# U_WE_BOX.net
KiCad netlist of a schematic drawn in EAGLE
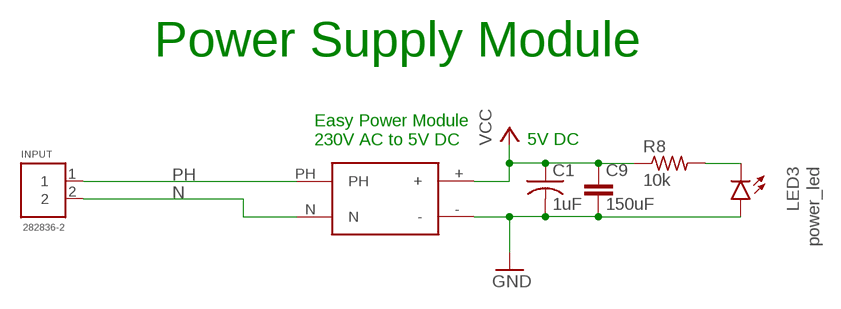
[diagram p0: schematic, sheet 1]
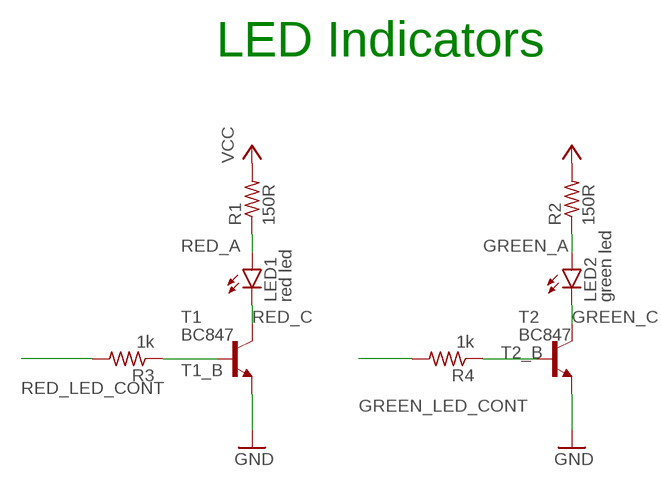
[diagram p1: schematic, sheet 2]
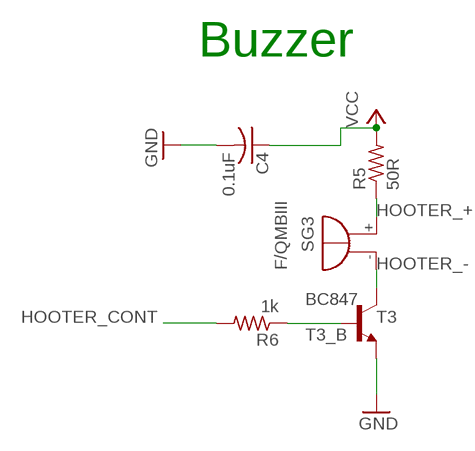
[diagram p2: schematic, sheet 3]
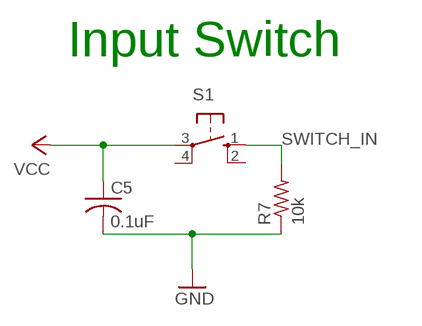
[diagram p3: schematic, sheet 4]
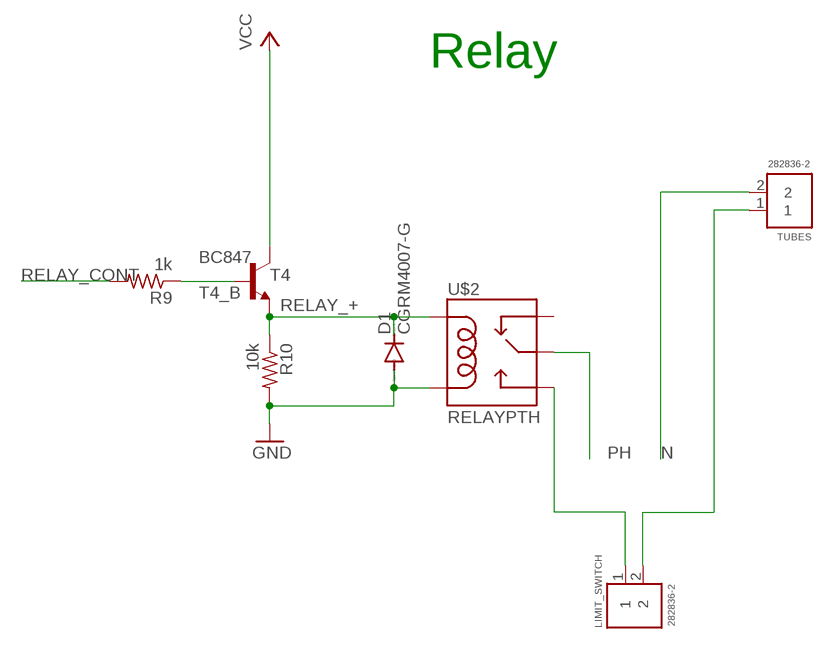
[diagram p4: schematic, sheet 5]
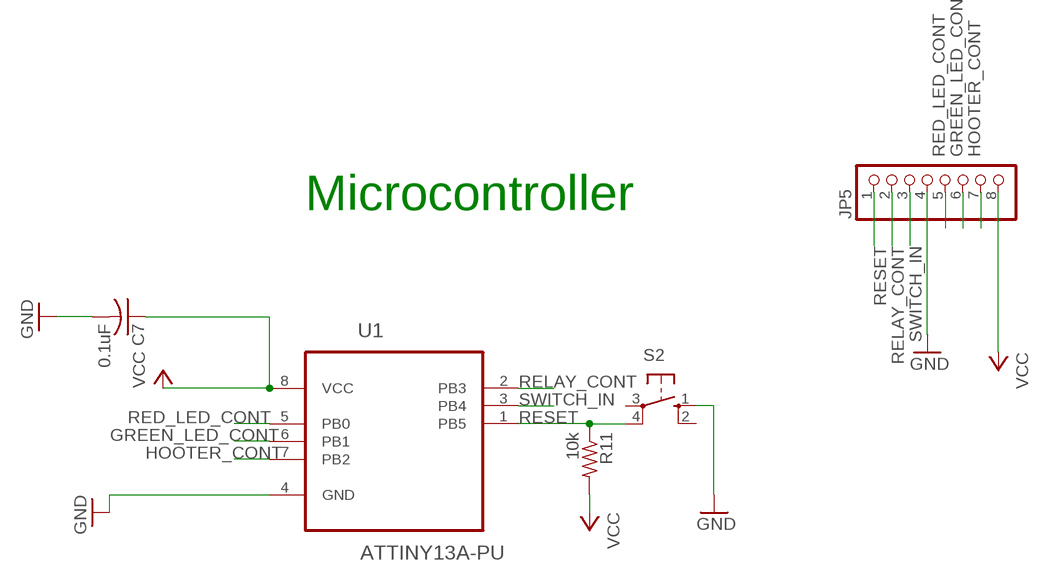
[diagram p5: schematic, sheet 6]

(export (version "E")
  (design (tool "Eeschema 10.0.6"))
  (components
    (comp (ref "C7")
      (value "0.1uF")
      (footprint "eagle-import:C1206K")
      (libsource (lib "eagle-import") (part "C-USC1206K"))
    )
    (comp (ref "JP5")
      (value "PINHD-1X8")
      (footprint "eagle-import:1X08")
      (libsource (lib "eagle-import") (part "PINHD-1X8"))
    )
    (comp (ref "R11")
      (value "10k")
      (footprint "eagle-import:R1206")
      (libsource (lib "eagle-import") (part "R-US_R1206"))
    )
    (comp (ref "S2")
      (value "10-XX")
      (footprint "eagle-import:B3F-10XX")
      (fields (field (name "MPN") "B3F-1000"))
      (libsource (lib "eagle-import") (part "10-XX"))
    )
    (comp (ref "U1")
      (value "ATTINY13A-PU")
      (footprint "eagle-import:DIP254P762X533-8")
      (fields (field (name "MF") "Microchip"))
      (libsource (lib "eagle-import") (part "ATTINY13A-PU"))
    )
    (comp (ref "D1")
      (value "CGRM4007-G")
      (footprint "eagle-import:SOD-123_MINI-SMA")
      (libsource (lib "eagle-import") (part "CGRM400-G7"))
    )
    (comp (ref "LIMIT_SWITCH")
      (value "282836-2")
      (footprint "eagle-import:CONN_282836-2")
      (fields (field (name "MF") "TE Connectivity"))
      (libsource (lib "eagle-import") (part "282836-2"))
    )
    (comp (ref "R9")
      (value "1k")
      (footprint "eagle-import:R1206")
      (libsource (lib "eagle-import") (part "R-US_R1206"))
    )
    (comp (ref "R10")
      (value "10k")
      (footprint "eagle-import:R1206")
      (libsource (lib "eagle-import") (part "R-US_R1206"))
    )
    (comp (ref "T4")
      (value "BC847")
      (footprint "eagle-import:SOT23")
      (libsource (lib "eagle-import") (part "BC847"))
    )
    (comp (ref "TUBES")
      (value "282836-2")
      (footprint "eagle-import:CONN_282836-2")
      (fields (field (name "MF") "TE Connectivity"))
      (libsource (lib "eagle-import") (part "282836-2"))
    )
    (comp (ref "U$2")
      (value "RELAYPTH")
      (footprint "eagle-import:SRD-05VDC-SL-C")
      (libsource (lib "eagle-import") (part "RELAYPTH"))
    )
    (comp (ref "C5")
      (value "0.1uF")
      (footprint "eagle-import:C1206K")
      (libsource (lib "eagle-import") (part "C-USC1206K"))
    )
    (comp (ref "R7")
      (value "10k")
      (footprint "eagle-import:R1206")
      (libsource (lib "eagle-import") (part "R-US_R1206"))
    )
    (comp (ref "S1")
      (value "40-XX")
      (footprint "eagle-import:B3F-40XX")
      (fields (field (name "MF") "OMRON COMPONENTS USA") (field (name "MPN") "B3F-4000"))
      (libsource (lib "eagle-import") (part "40-XX"))
    )
    (comp (ref "LED1")
      (value "red led")
      (footprint "eagle-import:CHIPLED_1206")
      (libsource (lib "eagle-import") (part "LEDCHIPLED_1206"))
    )
    (comp (ref "LED2")
      (value "green led")
      (footprint "eagle-import:CHIPLED_1206")
      (libsource (lib "eagle-import") (part "LEDCHIPLED_1206"))
    )
    (comp (ref "R1")
      (value "150R")
      (footprint "eagle-import:R1206")
      (libsource (lib "eagle-import") (part "R-US_R1206"))
    )
    (comp (ref "R2")
      (value "150R")
      (footprint "eagle-import:R1206")
      (libsource (lib "eagle-import") (part "R-US_R1206"))
    )
    (comp (ref "R3")
      (value "1k")
      (footprint "eagle-import:R1206")
      (libsource (lib "eagle-import") (part "R-US_R1206"))
    )
    (comp (ref "R4")
      (value "1k")
      (footprint "eagle-import:R1206")
      (libsource (lib "eagle-import") (part "R-US_R1206"))
    )
    (comp (ref "T1")
      (value "BC847")
      (footprint "eagle-import:SOT23")
      (libsource (lib "eagle-import") (part "BC847"))
    )
    (comp (ref "T2")
      (value "BC847")
      (footprint "eagle-import:SOT23")
      (libsource (lib "eagle-import") (part "BC847"))
    )
    (comp (ref "C1")
      (value "1uF")
      (footprint "eagle-import:C1206K")
      (libsource (lib "eagle-import") (part "C-USC1206K"))
    )
    (comp (ref "C9")
      (value "150uF")
      (footprint "eagle-import:C5B5")
      (libsource (lib "eagle-import") (part "C5/5"))
    )
    (comp (ref "INPUT")
      (value "282836-2")
      (footprint "eagle-import:CONN_282836-2")
      (fields (field (name "MF") "TE Connectivity"))
      (libsource (lib "eagle-import") (part "282836-2"))
    )
    (comp (ref "LED3")
      (value "power_led")
      (footprint "eagle-import:CHIPLED_1206")
      (libsource (lib "eagle-import") (part "LEDCHIPLED_1206"))
    )
    (comp (ref "R8")
      (value "10k")
      (footprint "eagle-import:M1206")
      (libsource (lib "eagle-import") (part "R-US_M1206"))
    )
    (comp (ref "U2")
      (value "AC/DCCONVERTER")
      (footprint "eagle-import:ACDC")
      (libsource (lib "eagle-import") (part "AC/DCCONVERTER"))
    )
    (comp (ref "C4")
      (value "0.1uF")
      (footprint "eagle-import:C1206K")
      (libsource (lib "eagle-import") (part "C-USC1206K"))
    )
    (comp (ref "R5")
      (value "50R")
      (footprint "eagle-import:R1206")
      (libsource (lib "eagle-import") (part "R-US_R1206"))
    )
    (comp (ref "R6")
      (value "1k")
      (footprint "eagle-import:R1206")
      (libsource (lib "eagle-import") (part "R-US_R1206"))
    )
    (comp (ref "SG3")
      (value "F/QMBIII")
      (footprint "eagle-import:F_QMBIII")
      (libsource (lib "eagle-import") (part "F/QMBIII"))
    )
    (comp (ref "T3")
      (value "BC847")
      (footprint "eagle-import:SOT23")
      (libsource (lib "eagle-import") (part "BC847"))
    )
  )
  (nets
    (net (code "1") (name "GND") (class "Default")
      (node (ref "C1") (pin "2") (pinfunction "2_2") (pintype "passive"))
      (node (ref "C4") (pin "2") (pinfunction "2_2") (pintype "passive"))
      (node (ref "C5") (pin "2") (pinfunction "2_2") (pintype "passive"))
      (node (ref "C7") (pin "2") (pinfunction "2_2") (pintype "passive"))
      (node (ref "C9") (pin "2") (pinfunction "2_2") (pintype "passive"))
      (node (ref "D1") (pin "A") (pinfunction "A_A") (pintype "passive"))
      (node (ref "JP5") (pin "4") (pinfunction "4_4") (pintype "passive"))
      (node (ref "LED3") (pin "A") (pinfunction "A_A") (pintype "passive"))
      (node (ref "R10") (pin "2") (pinfunction "2_2") (pintype "passive"))
      (node (ref "R7") (pin "1") (pinfunction "1_1") (pintype "passive"))
      (node (ref "S2") (pin "1") (pinfunction "S_1") (pintype "passive"))
      (node (ref "T1") (pin "2") (pinfunction "E_2") (pintype "passive"))
      (node (ref "T2") (pin "2") (pinfunction "E_2") (pintype "passive"))
      (node (ref "T3") (pin "2") (pinfunction "E_2") (pintype "passive"))
      (node (ref "U$2") (pin "COIL0") (pinfunction "COIL0_COIL0") (pintype "bidirectional"))
      (node (ref "U1") (pin "4") (pinfunction "GND_4") (pintype "passive"))
      (node (ref "U2") (pin "-") (pinfunction "-_-") (pintype "bidirectional"))
    )
    (net (code "2") (name "GREEN_A") (class "Default")
      (node (ref "LED2") (pin "A") (pinfunction "A_A") (pintype "passive"))
      (node (ref "R2") (pin "1") (pinfunction "1_1") (pintype "passive"))
    )
    (net (code "3") (name "GREEN_C") (class "Default")
      (node (ref "LED2") (pin "C") (pinfunction "C_C") (pintype "passive"))
      (node (ref "T2") (pin "3") (pinfunction "C_3") (pintype "passive"))
    )
    (net (code "4") (name "GREEN_LED_CONT") (class "Default")
      (node (ref "JP5") (pin "6") (pinfunction "6_6") (pintype "passive"))
      (node (ref "R4") (pin "2") (pinfunction "2_2") (pintype "passive"))
      (node (ref "U1") (pin "6") (pinfunction "PB1_6") (pintype "bidirectional"))
    )
    (net (code "5") (name "HOOTER_+") (class "Default")
      (node (ref "R5") (pin "1") (pinfunction "1_1") (pintype "passive"))
      (node (ref "SG3") (pin "+") (pinfunction "-_+") (pintype "passive"))
    )
    (net (code "6") (name "HOOTER_-") (class "Default")
      (node (ref "SG3") (pin "-") (pinfunction "+_-") (pintype "passive"))
      (node (ref "T3") (pin "3") (pinfunction "C_3") (pintype "passive"))
    )
    (net (code "7") (name "HOOTER_CONT") (class "Default")
      (node (ref "JP5") (pin "7") (pinfunction "7_7") (pintype "passive"))
      (node (ref "R6") (pin "2") (pinfunction "2_2") (pintype "passive"))
      (node (ref "U1") (pin "7") (pinfunction "PB2_7") (pintype "bidirectional"))
    )
    (net (code "8") (name "N") (class "Default")
      (node (ref "INPUT") (pin "2") (pinfunction "2_2") (pintype "passive"))
      (node (ref "TUBES") (pin "2") (pinfunction "2_2") (pintype "passive"))
      (node (ref "U2") (pin "N") (pinfunction "N_N") (pintype "bidirectional"))
    )
    (net (code "9") (name "Net-(LED3-PadC)") (class "Default")
      (node (ref "LED3") (pin "C") (pinfunction "C_C") (pintype "passive"))
      (node (ref "R8") (pin "2") (pinfunction "2_2") (pintype "passive"))
    )
    (net (code "10") (name "Net-(LIMIT_SWITCH-Pad1)") (class "Default")
      (node (ref "LIMIT_SWITCH") (pin "1") (pinfunction "1_1") (pintype "passive"))
      (node (ref "U$2") (pin "SWOPEN") (pinfunction "SWOPEN_SWOPEN") (pintype "bidirectional"))
    )
    (net (code "11") (name "Net-(LIMIT_SWITCH-Pad2)") (class "Default")
      (node (ref "LIMIT_SWITCH") (pin "2") (pinfunction "2_2") (pintype "passive"))
      (node (ref "TUBES") (pin "1") (pinfunction "1_1") (pintype "passive"))
    )
    (net (code "12") (name "PH") (class "Default")
      (node (ref "INPUT") (pin "1") (pinfunction "1_1") (pintype "passive"))
      (node (ref "U$2") (pin "SWCOMMON") (pinfunction "SWCOMMON_SWCOMMON") (pintype "bidirectional"))
      (node (ref "U2") (pin "PH") (pinfunction "PH_PH") (pintype "bidirectional"))
    )
    (net (code "13") (name "RED_A") (class "Default")
      (node (ref "LED1") (pin "A") (pinfunction "A_A") (pintype "passive"))
      (node (ref "R1") (pin "1") (pinfunction "1_1") (pintype "passive"))
    )
    (net (code "14") (name "RED_C") (class "Default")
      (node (ref "LED1") (pin "C") (pinfunction "C_C") (pintype "passive"))
      (node (ref "T1") (pin "3") (pinfunction "C_3") (pintype "passive"))
    )
    (net (code "15") (name "RED_LED_CONT") (class "Default")
      (node (ref "JP5") (pin "5") (pinfunction "5_5") (pintype "passive"))
      (node (ref "R3") (pin "2") (pinfunction "2_2") (pintype "passive"))
      (node (ref "U1") (pin "5") (pinfunction "PB0_5") (pintype "bidirectional"))
    )
    (net (code "16") (name "RELAY_+") (class "Default")
      (node (ref "D1") (pin "C") (pinfunction "C_C") (pintype "passive"))
      (node (ref "R10") (pin "1") (pinfunction "1_1") (pintype "passive"))
      (node (ref "T4") (pin "2") (pinfunction "E_2") (pintype "passive"))
      (node (ref "U$2") (pin "COIL1") (pinfunction "COIL1_COIL1") (pintype "bidirectional"))
    )
    (net (code "17") (name "RELAY_CONT") (class "Default")
      (node (ref "JP5") (pin "2") (pinfunction "2_2") (pintype "passive"))
      (node (ref "R9") (pin "2") (pinfunction "2_2") (pintype "passive"))
      (node (ref "U1") (pin "2") (pinfunction "PB3_2") (pintype "bidirectional"))
    )
    (net (code "18") (name "RESET") (class "Default")
      (node (ref "JP5") (pin "1") (pinfunction "1_1") (pintype "passive"))
      (node (ref "R11") (pin "1") (pinfunction "1_1") (pintype "passive"))
      (node (ref "S2") (pin "4") (pinfunction "P1_4") (pintype "passive"))
      (node (ref "U1") (pin "1") (pinfunction "PB5_1") (pintype "bidirectional"))
    )
    (net (code "19") (name "SWITCH_IN") (class "Default")
      (node (ref "JP5") (pin "3") (pinfunction "3_3") (pintype "passive"))
      (node (ref "R7") (pin "2") (pinfunction "2_2") (pintype "passive"))
      (node (ref "S1") (pin "1") (pinfunction "S_1") (pintype "passive"))
      (node (ref "U1") (pin "3") (pinfunction "PB4_3") (pintype "bidirectional"))
    )
    (net (code "20") (name "T1_B") (class "Default")
      (node (ref "R3") (pin "1") (pinfunction "1_1") (pintype "passive"))
      (node (ref "T1") (pin "1") (pinfunction "B_1") (pintype "passive"))
    )
    (net (code "21") (name "T2_B") (class "Default")
      (node (ref "R4") (pin "1") (pinfunction "1_1") (pintype "passive"))
      (node (ref "T2") (pin "1") (pinfunction "B_1") (pintype "passive"))
    )
    (net (code "22") (name "T3_B") (class "Default")
      (node (ref "R6") (pin "1") (pinfunction "1_1") (pintype "passive"))
      (node (ref "T3") (pin "1") (pinfunction "B_1") (pintype "passive"))
    )
    (net (code "23") (name "T4_B") (class "Default")
      (node (ref "R9") (pin "1") (pinfunction "1_1") (pintype "passive"))
      (node (ref "T4") (pin "1") (pinfunction "B_1") (pintype "passive"))
    )
    (net (code "24") (name "VCC") (class "Default")
      (node (ref "C1") (pin "1") (pinfunction "1_1") (pintype "passive"))
      (node (ref "C4") (pin "1") (pinfunction "1_1") (pintype "passive"))
      (node (ref "C5") (pin "1") (pinfunction "1_1") (pintype "passive"))
      (node (ref "C7") (pin "1") (pinfunction "1_1") (pintype "passive"))
      (node (ref "C9") (pin "1") (pinfunction "1_1") (pintype "passive"))
      (node (ref "JP5") (pin "8") (pinfunction "8_8") (pintype "passive"))
      (node (ref "R1") (pin "2") (pinfunction "2_2") (pintype "passive"))
      (node (ref "R11") (pin "2") (pinfunction "2_2") (pintype "passive"))
      (node (ref "R2") (pin "2") (pinfunction "2_2") (pintype "passive"))
      (node (ref "R5") (pin "2") (pinfunction "2_2") (pintype "passive"))
      (node (ref "R8") (pin "1") (pinfunction "1_1") (pintype "passive"))
      (node (ref "S1") (pin "3") (pinfunction "P_3") (pintype "passive"))
      (node (ref "T4") (pin "3") (pinfunction "C_3") (pintype "passive"))
      (node (ref "U1") (pin "8") (pinfunction "VCC_8") (pintype "power_in"))
      (node (ref "U2") (pin "+") (pinfunction "+_+") (pintype "bidirectional"))
    )
    (net (code "25") (name "unconnected-(S1-P1-Pad4)") (class "Default")
      (node (ref "S1") (pin "4") (pinfunction "P1_4") (pintype "passive"))
    )
    (net (code "26") (name "unconnected-(S1-S1-Pad2)") (class "Default")
      (node (ref "S1") (pin "2") (pinfunction "S1_2") (pintype "passive"))
    )
    (net (code "27") (name "unconnected-(S2-P-Pad3)") (class "Default")
      (node (ref "S2") (pin "3") (pinfunction "P_3") (pintype "passive"))
    )
    (net (code "28") (name "unconnected-(S2-S1-Pad2)") (class "Default")
      (node (ref "S2") (pin "2") (pinfunction "S1_2") (pintype "passive"))
    )
    (net (code "29") (name "unconnected-(U$2-SWCLOSE-PadSWCLOSED)") (class "Default")
      (node (ref "U$2") (pin "SWCLOSED") (pinfunction "SWCLOSE_SWCLOSED") (pintype "bidirectional"))
    )
  )
)
